# PCB_Sensor1_2.net
KiCad netlist of a schematic drawn in EAGLE
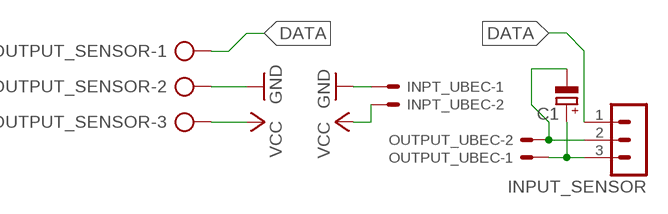
[diagram p0: schematic, sheet 1]

(export (version "E")
  (design (tool "Eeschema 10.0.6"))
  (components
    (comp (ref "C1")
      (value "CPOL-EUE2-5")
      (footprint "eagle-import:E2-5")
      (libsource (lib "eagle-import") (part "CPOL-EUE2-5"))
    )
    (comp (ref "INPT_UBEC")
      (value "22-23-2021")
      (footprint "eagle-import:22-23-2021")
      (fields (field (name "MF") "MOLEX"))
      (libsource (lib "eagle-import") (part "22-23-2021"))
    )
    (comp (ref "INPUT_SENSOR")
      (value "MA03-1")
      (footprint "eagle-import:MA03-1")
      (libsource (lib "eagle-import") (part "MA03-1"))
    )
    (comp (ref "OUTPUT_SENSOR")
      (value "AK500/3")
      (footprint "eagle-import:AK500_3")
      (libsource (lib "eagle-import") (part "AK500/3"))
    )
    (comp (ref "OUTPUT_UBEC")
      (value "22-23-2021")
      (footprint "eagle-import:22-23-2021")
      (fields (field (name "MF") "MOLEX"))
      (libsource (lib "eagle-import") (part "22-23-2021"))
    )
  )
  (nets
    (net (code "1") (name "DATA") (class "Default")
      (node (ref "INPUT_SENSOR") (pin "1") (pinfunction "1_1") (pintype "passive"))
      (node (ref "OUTPUT_SENSOR") (pin "1") (pinfunction "KL_1") (pintype "passive"))
    )
    (net (code "2") (name "GND") (class "Default")
      (node (ref "INPT_UBEC") (pin "1") (pinfunction "S_1") (pintype "passive"))
      (node (ref "OUTPUT_SENSOR") (pin "2") (pinfunction "KL_2") (pintype "passive"))
    )
    (net (code "3") (name "Net-(OUTPUT_UBECA-S)") (class "Default")
      (node (ref "C1") (pin "+") (pinfunction "+_+") (pintype "passive"))
      (node (ref "INPUT_SENSOR") (pin "3") (pinfunction "3_3") (pintype "passive"))
      (node (ref "OUTPUT_UBEC") (pin "1") (pinfunction "S_1") (pintype "passive"))
    )
    (net (code "4") (name "Net-(OUTPUT_UBECB-S)") (class "Default")
      (node (ref "C1") (pin "-") (pinfunction "-_-") (pintype "passive"))
      (node (ref "INPUT_SENSOR") (pin "2") (pinfunction "2_2") (pintype "passive"))
      (node (ref "OUTPUT_UBEC") (pin "2") (pinfunction "S_2") (pintype "passive"))
    )
    (net (code "5") (name "VCC") (class "Default")
      (node (ref "INPT_UBEC") (pin "2") (pinfunction "S_2") (pintype "passive"))
      (node (ref "OUTPUT_SENSOR") (pin "3") (pinfunction "KL_3") (pintype "passive"))
    )
  )
)
